# mpg-200-prototype_v4.net
KiCad netlist of a schematic drawn in EAGLE
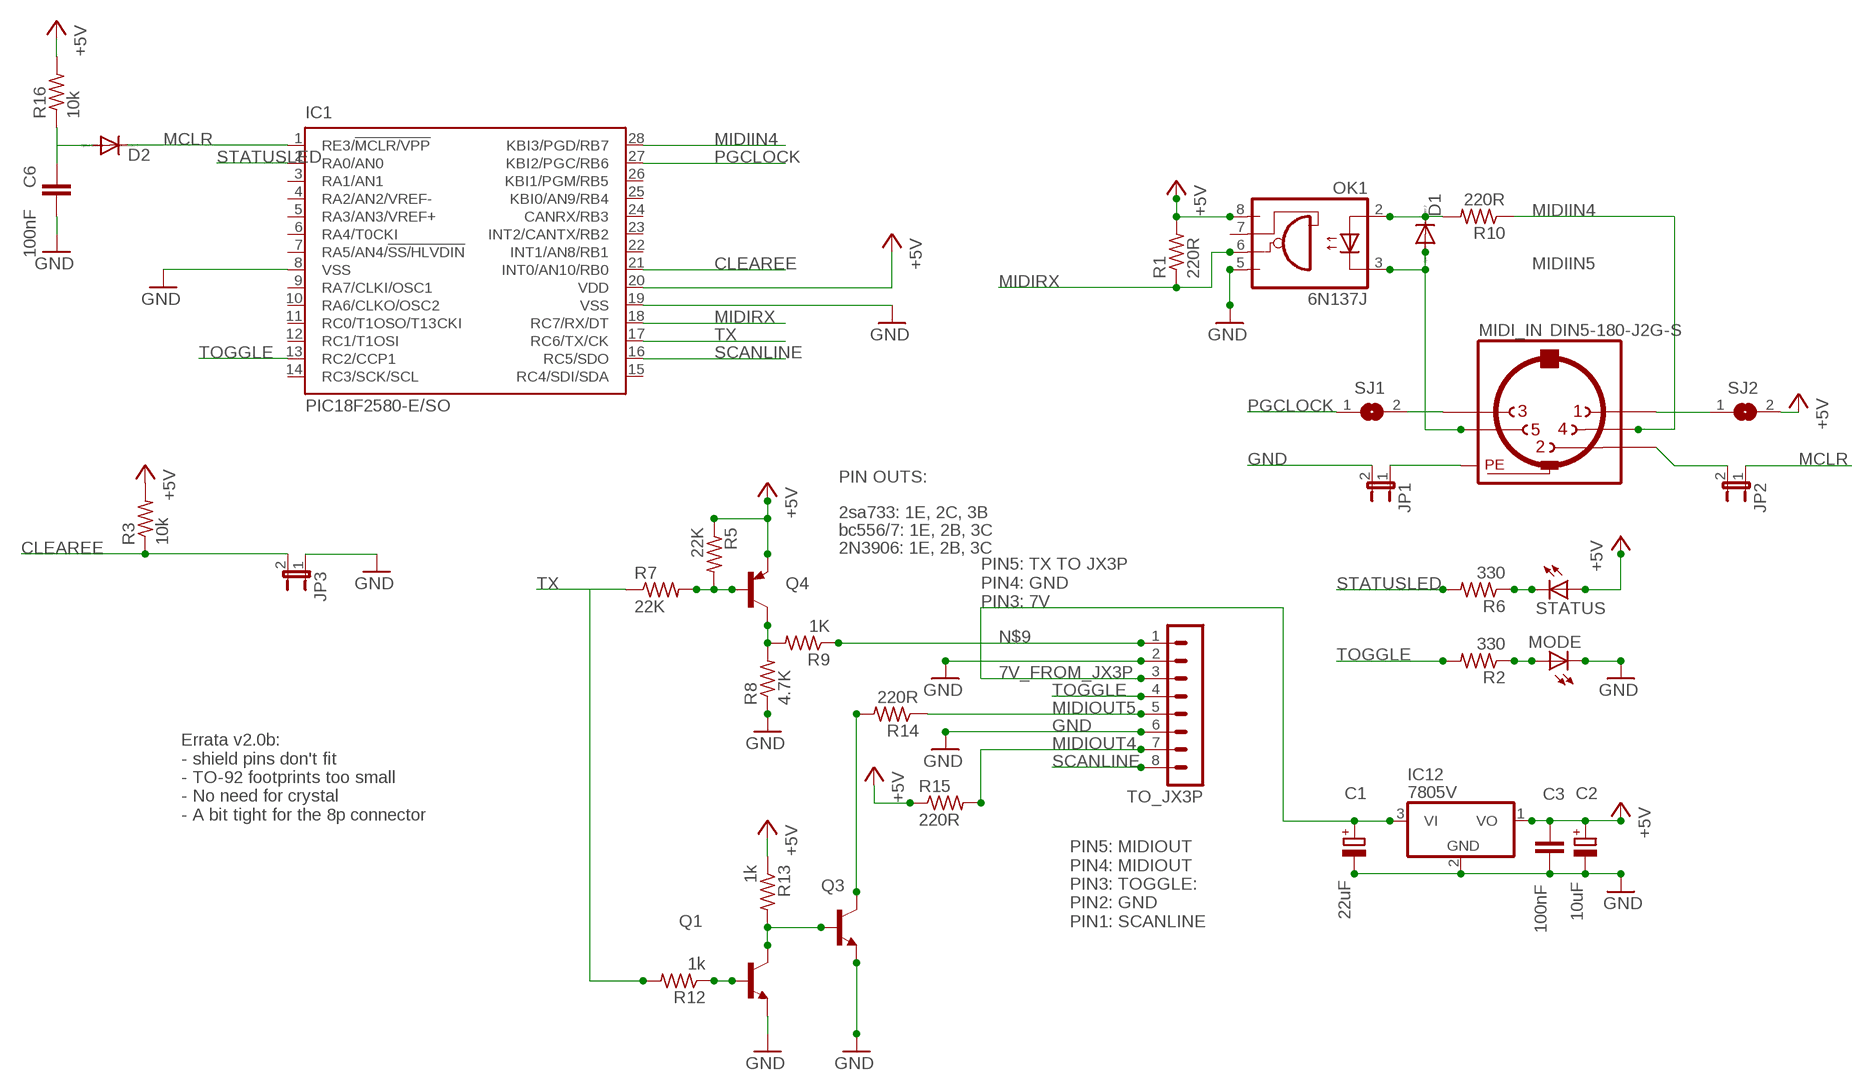
[diagram p0: schematic, sheet 1]

(export (version "E")
  (design (tool "Eeschema 10.0.6"))
  (components
    (comp (ref "C1")
      (value "22uF")
      (footprint "eagle-import:E2,5-5")
      (libsource (lib "eagle-import") (part "CPOL-EUE2.5-5"))
    )
    (comp (ref "C2")
      (value "10uF")
      (footprint "eagle-import:E2,5-5")
      (libsource (lib "eagle-import") (part "CPOL-EUE2.5-5"))
    )
    (comp (ref "C3")
      (value "100nF")
      (footprint "eagle-import:C0805")
      (libsource (lib "eagle-import") (part "C-EUC0805"))
    )
    (comp (ref "C6")
      (value "100nF")
      (footprint "eagle-import:C0805")
      (libsource (lib "eagle-import") (part "C-EUC0805"))
    )
    (comp (ref "D1")
      (value "DIODE-SOD80C")
      (footprint "eagle-import:SOD80C")
      (libsource (lib "eagle-import") (part "DIODE-SOD80C"))
    )
    (comp (ref "D2")
      (value "DIODE-SOD80C")
      (footprint "eagle-import:SOD80C")
      (libsource (lib "eagle-import") (part "DIODE-SOD80C"))
    )
    (comp (ref "IC1")
      (value "PIC18F2580-E/SO")
      (footprint "eagle-import:SO28W")
      (fields (field (name "MF") "MICROCHIP") (field (name "MPN") "PIC18F2580-I/SO"))
      (libsource (lib "eagle-import") (part "PIC18F280-E/SO5"))
    )
    (comp (ref "IC12")
      (value "7805V")
      (footprint "eagle-import:TO92")
      (libsource (lib "eagle-import") (part "78L05"))
    )
    (comp (ref "JP1")
      (value "JP1E")
      (footprint "eagle-import:JP1")
      (libsource (lib "eagle-import") (part "JP1E"))
    )
    (comp (ref "JP2")
      (value "JP1E")
      (footprint "eagle-import:JP1")
      (libsource (lib "eagle-import") (part "JP1E"))
    )
    (comp (ref "JP3")
      (value "JP1E")
      (footprint "eagle-import:JP1")
      (libsource (lib "eagle-import") (part "JP1E"))
    )
    (comp (ref "MIDI_IN")
      (value "DIN5-180-J2G-S")
      (footprint "eagle-import:DIN5-180-J-DUAL-GND-SHORT")
      (libsource (lib "eagle-import") (part "DIN5-180-J2G-S"))
    )
    (comp (ref "MODE")
      (value "LED3MM")
      (footprint "eagle-import:LED3MM")
      (libsource (lib "eagle-import") (part "LED3MM"))
    )
    (comp (ref "OK1")
      (value "6N137J")
      (footprint "eagle-import:DIL08-J")
      (libsource (lib "eagle-import") (part "6N137J"))
    )
    (comp (ref "Q1")
      (value "2N3904-NPN-TO92-EBC")
      (footprint "eagle-import:TO92-EBC")
      (libsource (lib "eagle-import") (part "-NPN-TO92-EBC2N3904"))
    )
    (comp (ref "Q3")
      (value "2N3904-NPN-TO92-EBC")
      (footprint "eagle-import:TO92-EBC")
      (libsource (lib "eagle-import") (part "-NPN-TO92-EBC2N3904"))
    )
    (comp (ref "Q4")
      (value "2N3906-PNP-TO92-EBC")
      (footprint "eagle-import:TO92-EBC")
      (libsource (lib "eagle-import") (part "-PNP-TO92-EBC2N3906"))
    )
    (comp (ref "R1")
      (value "220R")
      (footprint "eagle-import:R0805")
      (libsource (lib "eagle-import") (part "R-US_R0805"))
    )
    (comp (ref "R2")
      (value "330")
      (footprint "eagle-import:R0805")
      (libsource (lib "eagle-import") (part "R-US_R0805"))
    )
    (comp (ref "R3")
      (value "10k")
      (footprint "eagle-import:R0805")
      (libsource (lib "eagle-import") (part "R-US_R0805"))
    )
    (comp (ref "R5")
      (value "22K")
      (footprint "eagle-import:R0805")
      (libsource (lib "eagle-import") (part "R-US_R0805"))
    )
    (comp (ref "R6")
      (value "330")
      (footprint "eagle-import:R0805")
      (libsource (lib "eagle-import") (part "R-US_R0805"))
    )
    (comp (ref "R7")
      (value "22K")
      (footprint "eagle-import:R0805")
      (libsource (lib "eagle-import") (part "R-US_R0805"))
    )
    (comp (ref "R8")
      (value "4.7K")
      (footprint "eagle-import:R0805")
      (libsource (lib "eagle-import") (part "R-US_R0805"))
    )
    (comp (ref "R9")
      (value "1K")
      (footprint "eagle-import:R0805")
      (libsource (lib "eagle-import") (part "R-US_R0805"))
    )
    (comp (ref "R10")
      (value "220R")
      (footprint "eagle-import:R0805")
      (libsource (lib "eagle-import") (part "R-US_R0805"))
    )
    (comp (ref "R12")
      (value "1k")
      (footprint "eagle-import:R0805")
      (libsource (lib "eagle-import") (part "R-US_R0805"))
    )
    (comp (ref "R13")
      (value "1k")
      (footprint "eagle-import:R0805")
      (libsource (lib "eagle-import") (part "R-US_R0805"))
    )
    (comp (ref "R14")
      (value "220R")
      (footprint "eagle-import:R0805")
      (libsource (lib "eagle-import") (part "R-US_R0805"))
    )
    (comp (ref "R15")
      (value "220R")
      (footprint "eagle-import:R0805")
      (libsource (lib "eagle-import") (part "R-US_R0805"))
    )
    (comp (ref "R16")
      (value "10k")
      (footprint "eagle-import:R0805")
      (libsource (lib "eagle-import") (part "R-US_R0805"))
    )
    (comp (ref "SJ1") (value "SJ") (footprint "eagle-import:SJ") (libsource (lib "eagle-import") (part "SJ")))
    (comp (ref "SJ2") (value "SJ") (footprint "eagle-import:SJ") (libsource (lib "eagle-import") (part "SJ")))
    (comp (ref "STATUS")
      (value "LED3MM")
      (footprint "eagle-import:LED3MM")
      (libsource (lib "eagle-import") (part "LED3MM"))
    )
    (comp (ref "TO_JX3P")
      (value "MA08-1")
      (footprint "eagle-import:MA08-1")
      (libsource (lib "eagle-import") (part "MA08-1"))
    )
  )
  (nets
    (net (code "1") (name "+5V") (class "Default")
      (node (ref "C2") (pin "+") (pinfunction "+_+") (pintype "passive"))
      (node (ref "C3") (pin "1") (pinfunction "1_1") (pintype "passive"))
      (node (ref "IC1") (pin "20") (pinfunction "VDD_20") (pintype "power_in"))
      (node (ref "IC12") (pin "1") (pinfunction "VO_1") (pintype "passive"))
      (node (ref "OK1") (pin "8") (pinfunction "VCC_8") (pintype "passive"))
      (node (ref "Q4") (pin "E") (pinfunction "E_E") (pintype "passive"))
      (node (ref "R1") (pin "2") (pinfunction "2_2") (pintype "passive"))
      (node (ref "R13") (pin "1") (pinfunction "1_1") (pintype "passive"))
      (node (ref "R15") (pin "1") (pinfunction "1_1") (pintype "passive"))
      (node (ref "R16") (pin "2") (pinfunction "2_2") (pintype "passive"))
      (node (ref "R3") (pin "2") (pinfunction "2_2") (pintype "passive"))
      (node (ref "R5") (pin "1") (pinfunction "1_1") (pintype "passive"))
      (node (ref "SJ2") (pin "2") (pinfunction "2_2") (pintype "passive"))
      (node (ref "STATUS") (pin "A") (pinfunction "A_A") (pintype "passive"))
    )
    (net (code "2") (name "/7V_FROM_JX3P") (class "Default")
      (node (ref "C1") (pin "+") (pinfunction "+_+") (pintype "passive"))
      (node (ref "IC12") (pin "3") (pinfunction "VI_3") (pintype "input"))
      (node (ref "TO_JX3P") (pin "3") (pinfunction "3_3") (pintype "passive"))
    )
    (net (code "3") (name "/CLEAREE") (class "Default")
      (node (ref "IC1") (pin "21") (pinfunction "INT0/AN10/RB0_21") (pintype "bidirectional"))
      (node (ref "JP3") (pin "2") (pinfunction "2_2") (pintype "passive"))
      (node (ref "R3") (pin "1") (pinfunction "1_1") (pintype "passive"))
    )
    (net (code "4") (name "/MCLR") (class "Default")
      (node (ref "D2") (pin "C") (pinfunction "C_C") (pintype "passive"))
      (node (ref "IC1") (pin "1") (pinfunction "RE3/~{MCLR/VPP}_1") (pintype "input"))
      (node (ref "JP2") (pin "1") (pinfunction "1_1") (pintype "passive"))
    )
    (net (code "5") (name "/MIDIIN4") (class "Default")
      (node (ref "IC1") (pin "28") (pinfunction "KBI3/PGD/RB7_28") (pintype "bidirectional"))
      (node (ref "MIDI_IN") (pin "4") (pinfunction "4_4") (pintype "passive"))
      (node (ref "R10") (pin "1") (pinfunction "1_1") (pintype "passive"))
    )
    (net (code "6") (name "/MIDIIN5") (class "Default")
      (node (ref "D1") (pin "A") (pinfunction "A_A") (pintype "passive"))
      (node (ref "MIDI_IN") (pin "5") (pinfunction "5_5") (pintype "passive"))
      (node (ref "OK1") (pin "3") (pinfunction "C_3") (pintype "passive"))
    )
    (net (code "7") (name "/MIDIOUT4") (class "Default")
      (node (ref "R15") (pin "2") (pinfunction "2_2") (pintype "passive"))
      (node (ref "TO_JX3P") (pin "7") (pinfunction "7_7") (pintype "passive"))
    )
    (net (code "8") (name "/MIDIOUT5") (class "Default")
      (node (ref "R14") (pin "1") (pinfunction "1_1") (pintype "passive"))
      (node (ref "TO_JX3P") (pin "5") (pinfunction "5_5") (pintype "passive"))
    )
    (net (code "9") (name "/MIDIRX") (class "Default")
      (node (ref "IC1") (pin "18") (pinfunction "RC7/RX/DT_18") (pintype "bidirectional"))
      (node (ref "OK1") (pin "6") (pinfunction "VO_6") (pintype "passive"))
      (node (ref "R1") (pin "1") (pinfunction "1_1") (pintype "passive"))
    )
    (net (code "10") (name "/N$9") (class "Default")
      (node (ref "R9") (pin "1") (pinfunction "1_1") (pintype "passive"))
      (node (ref "TO_JX3P") (pin "1") (pinfunction "1_1") (pintype "passive"))
    )
    (net (code "11") (name "/PGCLOCK") (class "Default")
      (node (ref "IC1") (pin "27") (pinfunction "KBI2/PGC/RB6_27") (pintype "bidirectional"))
      (node (ref "SJ1") (pin "1") (pinfunction "1_1") (pintype "passive"))
    )
    (net (code "12") (name "/SCANLINE") (class "Default")
      (node (ref "IC1") (pin "16") (pinfunction "RC5/SDO_16") (pintype "bidirectional"))
      (node (ref "TO_JX3P") (pin "8") (pinfunction "8_8") (pintype "passive"))
    )
    (net (code "13") (name "/STATUSLED") (class "Default")
      (node (ref "IC1") (pin "2") (pinfunction "RA0/AN0_2") (pintype "bidirectional"))
      (node (ref "R6") (pin "2") (pinfunction "2_2") (pintype "passive"))
    )
    (net (code "14") (name "/TOGGLE") (class "Default")
      (node (ref "IC1") (pin "13") (pinfunction "RC2/CCP1_13") (pintype "bidirectional"))
      (node (ref "R2") (pin "2") (pinfunction "2_2") (pintype "passive"))
      (node (ref "TO_JX3P") (pin "4") (pinfunction "4_4") (pintype "passive"))
    )
    (net (code "15") (name "/TX") (class "Default")
      (node (ref "IC1") (pin "17") (pinfunction "RC6/TX/CK_17") (pintype "bidirectional"))
      (node (ref "R12") (pin "2") (pinfunction "2_2") (pintype "passive"))
      (node (ref "R7") (pin "1") (pinfunction "1_1") (pintype "passive"))
    )
    (net (code "16") (name "GND") (class "Default")
      (node (ref "C1") (pin "-") (pinfunction "-_-") (pintype "passive"))
      (node (ref "C2") (pin "-") (pinfunction "-_-") (pintype "passive"))
      (node (ref "C3") (pin "2") (pinfunction "2_2") (pintype "passive"))
      (node (ref "C6") (pin "2") (pinfunction "2_2") (pintype "passive"))
      (node (ref "IC1") (pin "19") (pinfunction "VSS_19") (pintype "power_in"))
      (node (ref "IC1") (pin "8") (pinfunction "VSS_8") (pintype "power_in"))
      (node (ref "IC12") (pin "2") (pinfunction "GND_2") (pintype "passive"))
      (node (ref "JP1") (pin "2") (pinfunction "2_2") (pintype "passive"))
      (node (ref "JP3") (pin "1") (pinfunction "1_1") (pintype "passive"))
      (node (ref "MODE") (pin "K") (pinfunction "C_K") (pintype "passive"))
      (node (ref "OK1") (pin "5") (pinfunction "GND_5") (pintype "passive"))
      (node (ref "Q1") (pin "E") (pinfunction "E_E") (pintype "passive"))
      (node (ref "Q3") (pin "E") (pinfunction "E_E") (pintype "passive"))
      (node (ref "R8") (pin "1") (pinfunction "1_1") (pintype "passive"))
      (node (ref "TO_JX3P") (pin "2") (pinfunction "2_2") (pintype "passive"))
      (node (ref "TO_JX3P") (pin "6") (pinfunction "6_6") (pintype "passive"))
    )
    (net (code "17") (name "Net-(C6-Pad1)") (class "Default")
      (node (ref "C6") (pin "1") (pinfunction "1_1") (pintype "passive"))
      (node (ref "D2") (pin "A") (pinfunction "A_A") (pintype "passive"))
      (node (ref "R16") (pin "1") (pinfunction "1_1") (pintype "passive"))
    )
    (net (code "18") (name "Net-(JP1-Pad1)") (class "Default")
      (node (ref "JP1") (pin "1") (pinfunction "1_1") (pintype "passive"))
      (node (ref "MIDI_IN") (pin "PE") (pinfunction "PE_PE") (pintype "power_in"))
      (node (ref "MIDI_IN") (pin "PE@1") (pinfunction "PE_PE@1") (pintype "power_in"))
      (node (ref "MIDI_IN") (pin "PE@2") (pinfunction "PE_PE@2") (pintype "power_in"))
      (node (ref "MIDI_IN") (pin "PE@3") (pinfunction "PE_PE@3") (pintype "power_in"))
    )
    (net (code "19") (name "Net-(JP2-Pad2)") (class "Default")
      (node (ref "JP2") (pin "2") (pinfunction "2_2") (pintype "passive"))
      (node (ref "MIDI_IN") (pin "2") (pinfunction "2_2") (pintype "passive"))
    )
    (net (code "20") (name "Net-(MIDI_IN-Pad1)") (class "Default")
      (node (ref "MIDI_IN") (pin "1") (pinfunction "1_1") (pintype "passive"))
      (node (ref "SJ2") (pin "1") (pinfunction "1_1") (pintype "passive"))
    )
    (net (code "21") (name "Net-(MIDI_IN-Pad3)") (class "Default")
      (node (ref "MIDI_IN") (pin "3") (pinfunction "3_3") (pintype "passive"))
      (node (ref "SJ1") (pin "2") (pinfunction "2_2") (pintype "passive"))
    )
    (net (code "22") (name "Net-(MODE-PadA)") (class "Default")
      (node (ref "MODE") (pin "A") (pinfunction "A_A") (pintype "passive"))
      (node (ref "R2") (pin "1") (pinfunction "1_1") (pintype "passive"))
    )
    (net (code "23") (name "Net-(OK1-A)") (class "Default")
      (node (ref "D1") (pin "C") (pinfunction "C_C") (pintype "passive"))
      (node (ref "OK1") (pin "2") (pinfunction "A_2") (pintype "passive"))
      (node (ref "R10") (pin "2") (pinfunction "2_2") (pintype "passive"))
    )
    (net (code "24") (name "Net-(Q1-PadB)") (class "Default")
      (node (ref "Q1") (pin "B") (pinfunction "B_B") (pintype "passive"))
      (node (ref "R12") (pin "1") (pinfunction "1_1") (pintype "passive"))
    )
    (net (code "25") (name "Net-(Q1-PadC)") (class "Default")
      (node (ref "Q1") (pin "C") (pinfunction "C_C") (pintype "passive"))
      (node (ref "Q3") (pin "B") (pinfunction "B_B") (pintype "passive"))
      (node (ref "R13") (pin "2") (pinfunction "2_2") (pintype "passive"))
    )
    (net (code "26") (name "Net-(Q3-PadC)") (class "Default")
      (node (ref "Q3") (pin "C") (pinfunction "C_C") (pintype "passive"))
      (node (ref "R14") (pin "2") (pinfunction "2_2") (pintype "passive"))
    )
    (net (code "27") (name "Net-(Q4-PadB)") (class "Default")
      (node (ref "Q4") (pin "B") (pinfunction "B_B") (pintype "passive"))
      (node (ref "R5") (pin "2") (pinfunction "2_2") (pintype "passive"))
      (node (ref "R7") (pin "2") (pinfunction "2_2") (pintype "passive"))
    )
    (net (code "28") (name "Net-(Q4-PadC)") (class "Default")
      (node (ref "Q4") (pin "C") (pinfunction "C_C") (pintype "passive"))
      (node (ref "R8") (pin "2") (pinfunction "2_2") (pintype "passive"))
      (node (ref "R9") (pin "2") (pinfunction "2_2") (pintype "passive"))
    )
    (net (code "29") (name "Net-(STATUS-C)") (class "Default")
      (node (ref "R6") (pin "1") (pinfunction "1_1") (pintype "passive"))
      (node (ref "STATUS") (pin "K") (pinfunction "C_K") (pintype "passive"))
    )
    (net (code "30") (name "unconnected-(IC1-CANRX{slash}RB3-Pad24)") (class "Default")
      (node (ref "IC1") (pin "24") (pinfunction "CANRX/RB3_24") (pintype "bidirectional"))
    )
    (net (code "31") (name "unconnected-(IC1-INT1{slash}AN8{slash}RB1-Pad22)") (class "Default")
      (node (ref "IC1") (pin "22") (pinfunction "INT1/AN8/RB1_22") (pintype "bidirectional"))
    )
    (net (code "32") (name "unconnected-(IC1-INT2{slash}CANTX{slash}RB2-Pad23)") (class "Default")
      (node (ref "IC1") (pin "23") (pinfunction "INT2/CANTX/RB2_23") (pintype "bidirectional"))
    )
    (net (code "33") (name "unconnected-(IC1-KBI0{slash}AN9{slash}RB4-Pad25)") (class "Default")
      (node (ref "IC1") (pin "25") (pinfunction "KBI0/AN9/RB4_25") (pintype "bidirectional"))
    )
    (net (code "34") (name "unconnected-(IC1-KBI1{slash}PGM{slash}RB5-Pad26)") (class "Default")
      (node (ref "IC1") (pin "26") (pinfunction "KBI1/PGM/RB5_26") (pintype "bidirectional"))
    )
    (net (code "35") (name "unconnected-(IC1-RA1{slash}AN1-Pad3)") (class "Default")
      (node (ref "IC1") (pin "3") (pinfunction "RA1/AN1_3") (pintype "bidirectional"))
    )
    (net (code "36") (name "unconnected-(IC1-RA2{slash}AN2{slash}VREF--Pad4)") (class "Default")
      (node (ref "IC1") (pin "4") (pinfunction "RA2/AN2/VREF-_4") (pintype "bidirectional"))
    )
    (net (code "37") (name "unconnected-(IC1-RA3{slash}AN3{slash}VREF+-Pad5)") (class "Default")
      (node (ref "IC1") (pin "5") (pinfunction "RA3/AN3/VREF+_5") (pintype "bidirectional"))
    )
    (net (code "38") (name "unconnected-(IC1-RA4{slash}T0CKI-Pad6)") (class "Default")
      (node (ref "IC1") (pin "6") (pinfunction "RA4/T0CKI_6") (pintype "bidirectional"))
    )
    (net (code "39") (name "unconnected-(IC1-RA5{slash}AN4{slash}~{SS{slash}HLVDIN}-Pad7)") (class "Default")
      (node (ref "IC1") (pin "7") (pinfunction "RA5/AN4/~{SS/HLVDIN}_7") (pintype "bidirectional"))
    )
    (net (code "40") (name "unconnected-(IC1-RA6{slash}CLKO{slash}OSC2-Pad10)") (class "Default")
      (node (ref "IC1") (pin "10") (pinfunction "RA6/CLKO/OSC2_10") (pintype "output"))
    )
    (net (code "41") (name "unconnected-(IC1-RA7{slash}CLKI{slash}OSC1-Pad9)") (class "Default")
      (node (ref "IC1") (pin "9") (pinfunction "RA7/CLKI/OSC1_9") (pintype "input"))
    )
    (net (code "42") (name "unconnected-(IC1-RC0{slash}T1OSO{slash}T13CKI-Pad11)") (class "Default")
      (node (ref "IC1") (pin "11") (pinfunction "RC0/T1OSO/T13CKI_11") (pintype "bidirectional"))
    )
    (net (code "43") (name "unconnected-(IC1-RC1{slash}T1OSI-Pad12)") (class "Default")
      (node (ref "IC1") (pin "12") (pinfunction "RC1/T1OSI_12") (pintype "bidirectional"))
    )
    (net (code "44") (name "unconnected-(IC1-RC3{slash}SCK{slash}SCL-Pad14)") (class "Default")
      (node (ref "IC1") (pin "14") (pinfunction "RC3/SCK/SCL_14") (pintype "bidirectional"))
    )
    (net (code "45") (name "unconnected-(IC1-RC4{slash}SDI{slash}SDA-Pad15)") (class "Default")
      (node (ref "IC1") (pin "15") (pinfunction "RC4/SDI/SDA_15") (pintype "bidirectional"))
    )
    (net (code "46") (name "unconnected-(OK1-VE-Pad7)") (class "Default")
      (node (ref "OK1") (pin "7") (pinfunction "VE_7") (pintype "passive"))
    )
  )
)
